# 06_-_Voltage_Sense.net
KiCad netlist of a schematic drawn in Altium Designer
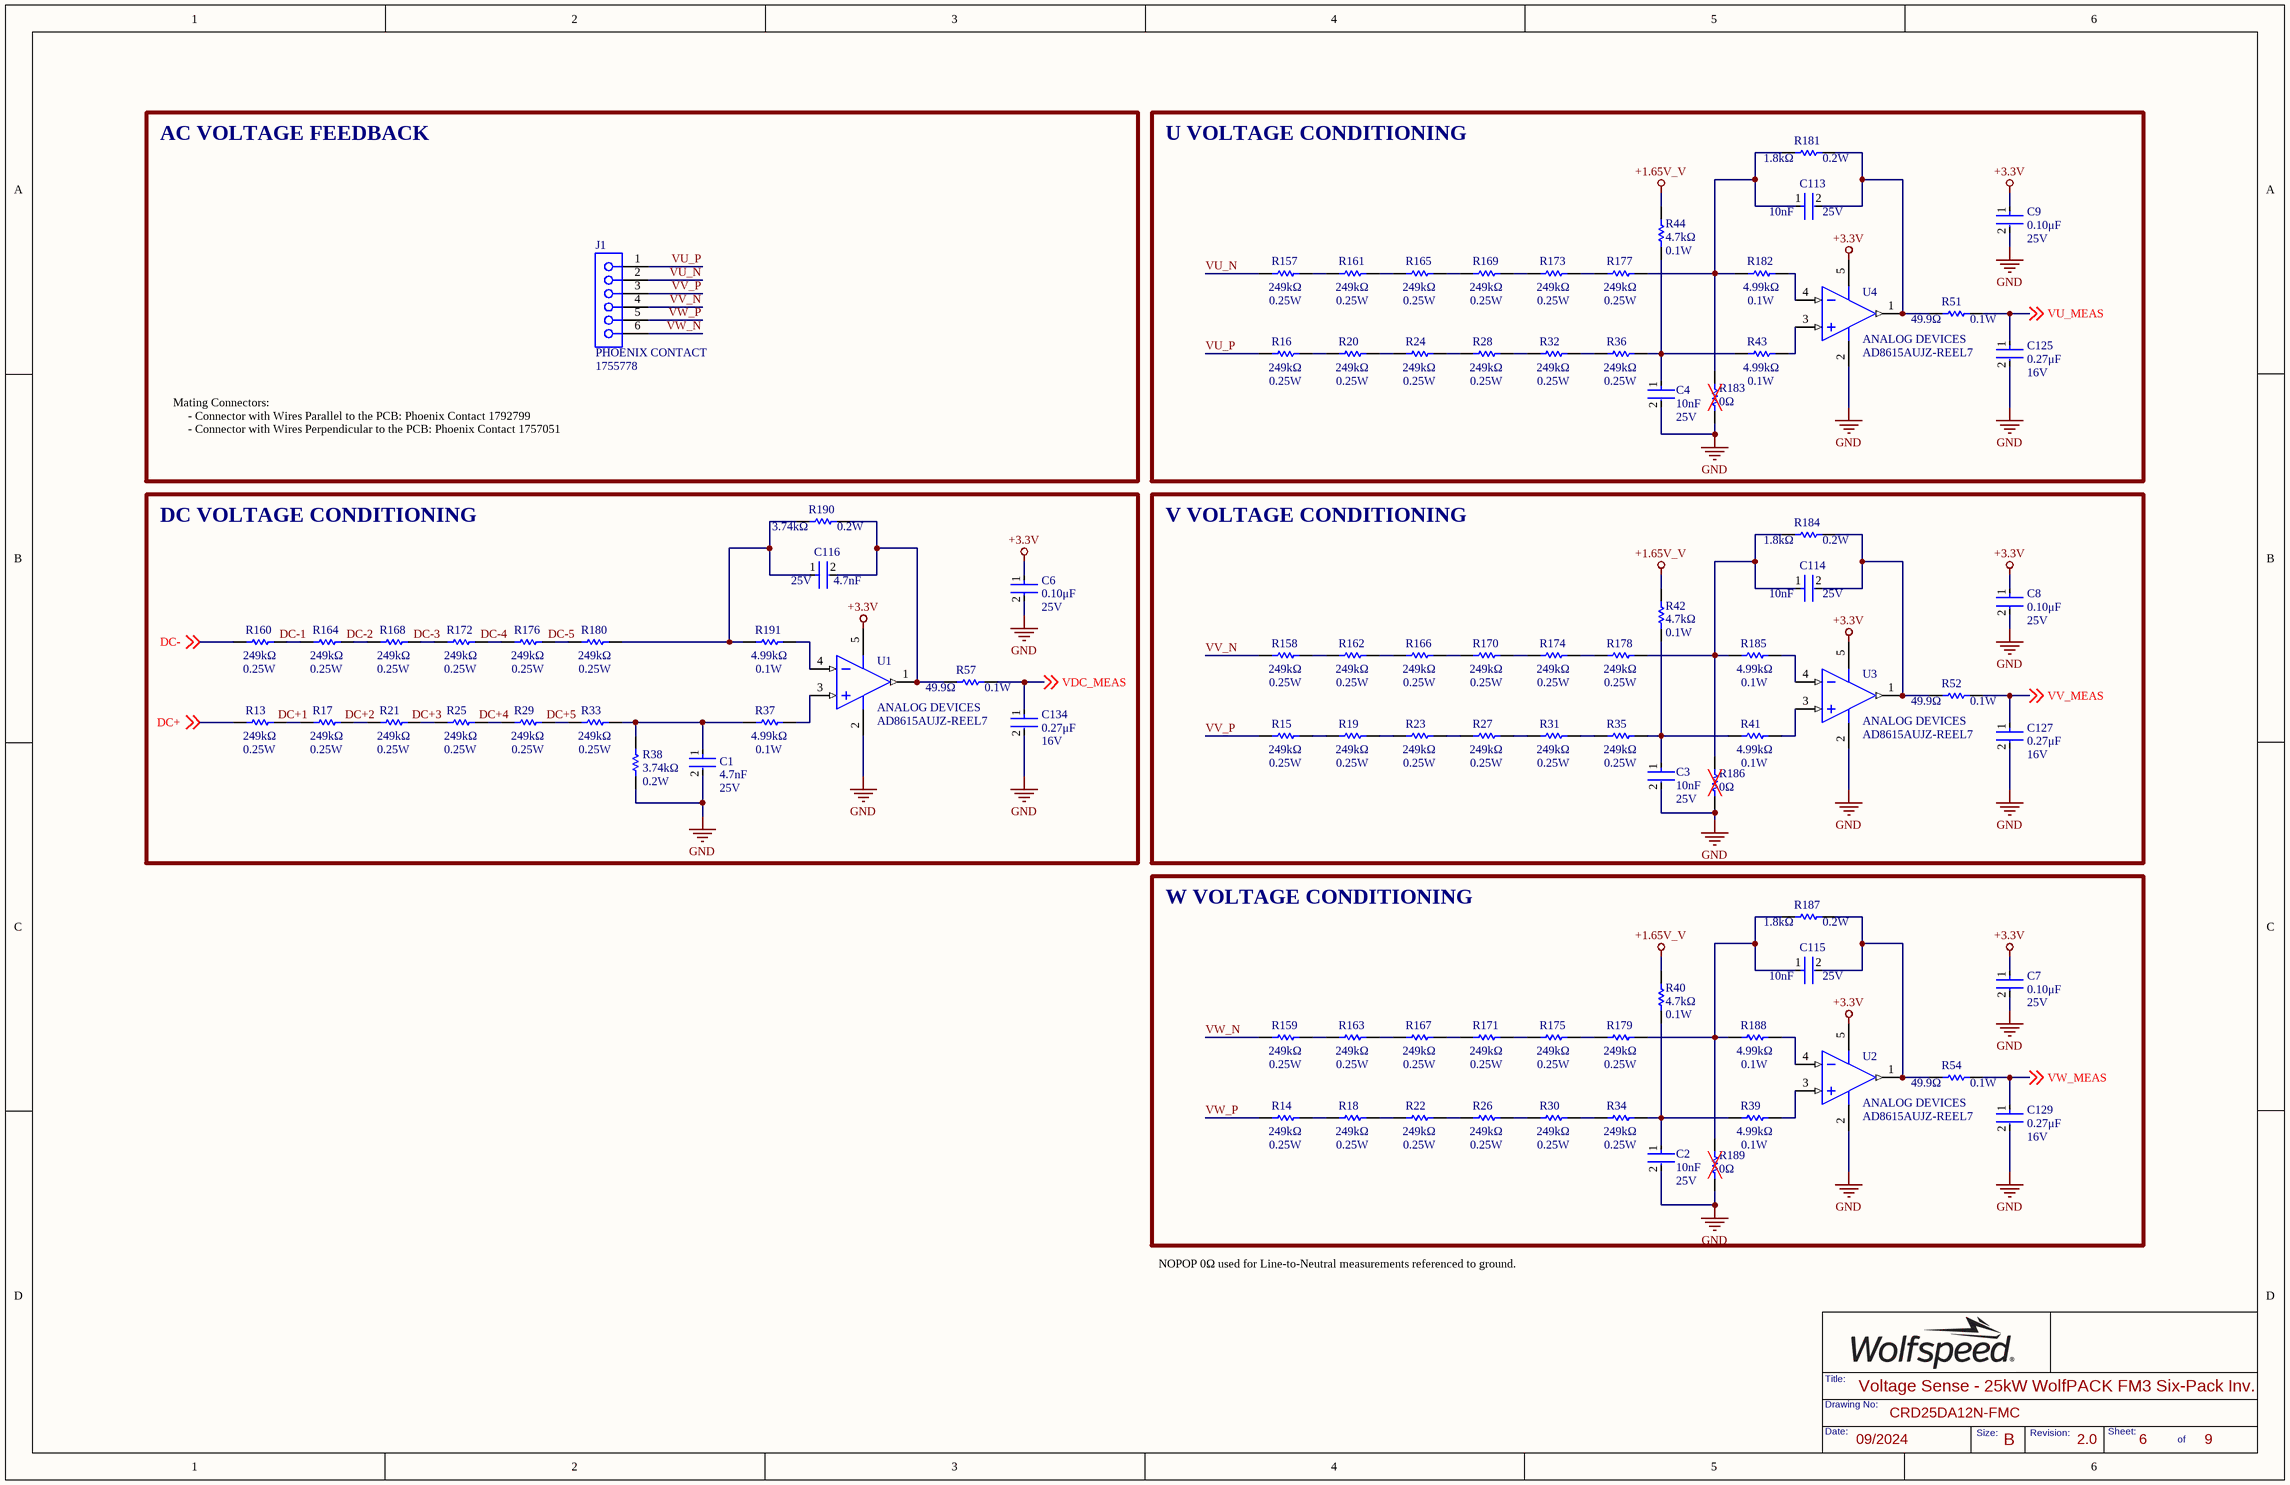
[diagram p0: 06 - Voltage Sense.SchDoc]

(export (version "E")
  (design (tool "Eeschema 10.0.6"))
  (components
    (comp (ref "C1")
      (value "C0603C472K3RAC7867")
      (footprint "FP-C0603C-CF-IPC_B")
      (description "CAP CER 4700PF 25V 10% X7R 0603")
      (fields
        (field (name "MANUFACTURER") "KEMET")
        (field (name "MANUFACTURER PART NUMBER") "C0603C472K3RACTU")
        (field (name "VOLTAGE RATING") "25V")
        (field (name "CAPACITANCE") "4.7nF")
      )
      (libsource (lib "Inverter_25kW") (part "C0603C472K3RAC7867"))
    )
    (comp (ref "C2")
      (value "10nF")
      (footprint "FP-C0603C-CF-IPC_B")
      (description "CAP CER 10000PF 25V X7R 0603")
      (fields
        (field (name "MANUFACTURER") "SAMSUNG")
        (field (name "MANUFACTURER PART NUMBER") "CL10B103KA8WPNC")
        (field (name "VOLTAGE RATING") "25V")
      )
      (libsource (lib "Inverter_25kW") (part "CL10B103KA8WPNC"))
    )
    (comp (ref "C3")
      (value "10nF")
      (footprint "FP-C0603C-CF-IPC_B")
      (description "CAP CER 10000PF 25V X7R 0603")
      (fields
        (field (name "MANUFACTURER") "SAMSUNG")
        (field (name "MANUFACTURER PART NUMBER") "CL10B103KA8WPNC")
        (field (name "VOLTAGE RATING") "25V")
      )
      (libsource (lib "Inverter_25kW") (part "CL10B103KA8WPNC"))
    )
    (comp (ref "C4")
      (value "10nF")
      (footprint "FP-C0603C-CF-IPC_B")
      (description "CAP CER 10000PF 25V X7R 0603")
      (fields
        (field (name "MANUFACTURER") "SAMSUNG")
        (field (name "MANUFACTURER PART NUMBER") "CL10B103KA8WPNC")
        (field (name "VOLTAGE RATING") "25V")
      )
      (libsource (lib "Inverter_25kW") (part "CL10B103KA8WPNC"))
    )
    (comp (ref "C6")
      (value "C0603C104K3RACTU")
      (footprint "FP-C0603C-CF-IPC_B")
      (description "CAP CER 0.1UF 25V X7R 0603")
      (fields
        (field (name "VOLTAGE RATING") "25V")
        (field (name "OCTOPART") "https://octopart.com/c0603c104k3ractu-kemet-127541")
        (field (name "MANUFACTURER") "KEMET")
        (field (name "CAPACITANCE") "0.10μF")
      )
      (libsource (lib "Altium Content Vault") (part "b4654b650e69147ec39a6b967a45e02"))
    )
    (comp (ref "C7")
      (value "C0603C104K3RACTU")
      (footprint "FP-C0603C-CF-IPC_B")
      (description "CAP CER 0.1UF 25V X7R 0603")
      (fields
        (field (name "VOLTAGE RATING") "25V")
        (field (name "OCTOPART") "https://octopart.com/c0603c104k3ractu-kemet-127541")
        (field (name "MANUFACTURER") "KEMET")
        (field (name "CAPACITANCE") "0.10μF")
      )
      (libsource (lib "Altium Content Vault") (part "b4654b650e69147ec39a6b967a45e02"))
    )
    (comp (ref "C8")
      (value "C0603C104K3RACTU")
      (footprint "FP-C0603C-CF-IPC_B")
      (description "CAP CER 0.1UF 25V X7R 0603")
      (fields
        (field (name "VOLTAGE RATING") "25V")
        (field (name "OCTOPART") "https://octopart.com/c0603c104k3ractu-kemet-127541")
        (field (name "MANUFACTURER") "KEMET")
        (field (name "CAPACITANCE") "0.10μF")
      )
      (libsource (lib "Altium Content Vault") (part "b4654b650e69147ec39a6b967a45e02"))
    )
    (comp (ref "C9")
      (value "C0603C104K3RACTU")
      (footprint "FP-C0603C-CF-IPC_B")
      (description "CAP CER 0.1UF 25V X7R 0603")
      (fields
        (field (name "VOLTAGE RATING") "25V")
        (field (name "OCTOPART") "https://octopart.com/c0603c104k3ractu-kemet-127541")
        (field (name "MANUFACTURER") "KEMET")
        (field (name "CAPACITANCE") "0.10μF")
      )
      (libsource (lib "Altium Content Vault") (part "b4654b650e69147ec39a6b967a45e02"))
    )
    (comp (ref "C113")
      (value "10nF")
      (footprint "FP-C0603C-CF-IPC_B")
      (description "CAP CER 10000PF 25V X7R 0603")
      (fields
        (field (name "MANUFACTURER") "SAMSUNG")
        (field (name "MANUFACTURER PART NUMBER") "CL10B103KA8WPNC")
        (field (name "VOLTAGE RATING") "25V")
      )
      (libsource (lib "Inverter_25kW") (part "CL10B103KA8WPNC"))
    )
    (comp (ref "C114")
      (value "10nF")
      (footprint "FP-C0603C-CF-IPC_B")
      (description "CAP CER 10000PF 25V X7R 0603")
      (fields
        (field (name "MANUFACTURER") "SAMSUNG")
        (field (name "MANUFACTURER PART NUMBER") "CL10B103KA8WPNC")
        (field (name "VOLTAGE RATING") "25V")
      )
      (libsource (lib "Inverter_25kW") (part "CL10B103KA8WPNC"))
    )
    (comp (ref "C115")
      (value "10nF")
      (footprint "FP-C0603C-CF-IPC_B")
      (description "CAP CER 10000PF 25V X7R 0603")
      (fields
        (field (name "MANUFACTURER") "SAMSUNG")
        (field (name "MANUFACTURER PART NUMBER") "CL10B103KA8WPNC")
        (field (name "VOLTAGE RATING") "25V")
      )
      (libsource (lib "Inverter_25kW") (part "CL10B103KA8WPNC"))
    )
    (comp (ref "C116")
      (value "C0603C472K3RAC7867")
      (footprint "FP-C0603C-CF-IPC_B")
      (description "CAP CER 4700PF 25V 10% X7R 0603")
      (fields
        (field (name "MANUFACTURER") "KEMET")
        (field (name "MANUFACTURER PART NUMBER") "C0603C472K3RACTU")
        (field (name "VOLTAGE RATING") "25V")
        (field (name "CAPACITANCE") "4.7nF")
      )
      (libsource (lib "Inverter_25kW") (part "C0603C472K3RAC7867"))
    )
    (comp (ref "C125")
      (value "GCM188R71C274KA37D")
      (footprint "FP-GCM188-0_1-IPC_A")
      (description "CAP CER 0.27UF 16V X7R 0603")
      (fields
        (field (name "VOLTAGE RATING (DC)") "16V")
        (field (name "CAPACITANCE") "0.27μF")
        (field (name "TOLERANCE") "10%")
        (field (name "MANUFACTURER") "MURATA")
      )
      (libsource (lib "Altium Content Vault") (part "02cd4be3c70576c341d710602a673aa"))
    )
    (comp (ref "C127")
      (value "GCM188R71C274KA37D")
      (footprint "FP-GCM188-0_1-IPC_A")
      (description "CAP CER 0.27UF 16V X7R 0603")
      (fields
        (field (name "VOLTAGE RATING (DC)") "16V")
        (field (name "CAPACITANCE") "0.27μF")
        (field (name "TOLERANCE") "10%")
        (field (name "MANUFACTURER") "MURATA")
      )
      (libsource (lib "Altium Content Vault") (part "02cd4be3c70576c341d710602a673aa"))
    )
    (comp (ref "C129")
      (value "GCM188R71C274KA37D")
      (footprint "FP-GCM188-0_1-IPC_A")
      (description "CAP CER 0.27UF 16V X7R 0603")
      (fields
        (field (name "VOLTAGE RATING (DC)") "16V")
        (field (name "CAPACITANCE") "0.27μF")
        (field (name "TOLERANCE") "10%")
        (field (name "MANUFACTURER") "MURATA")
      )
      (libsource (lib "Altium Content Vault") (part "02cd4be3c70576c341d710602a673aa"))
    )
    (comp (ref "C134")
      (value "GCM188R71C274KA37D")
      (footprint "FP-GCM188-0_1-IPC_A")
      (description "CAP CER 0.27UF 16V X7R 0603")
      (fields
        (field (name "VOLTAGE RATING (DC)") "16V")
        (field (name "CAPACITANCE") "0.27μF")
        (field (name "TOLERANCE") "10%")
        (field (name "MANUFACTURER") "MURATA")
      )
      (libsource (lib "Altium Content Vault") (part "02cd4be3c70576c341d710602a673aa"))
    )
    (comp (ref "J1")
      (value "1755778")
      (footprint "Inverter_25kW:1755778")
      (description "TERM BLOCK HDR 6POS VERT 5.08MM")
      (fields
        (field (name "MANUFACTURER") "PHOENIX CONTACT")
        (field (name "VOLTAGE") "300V")
        (field (name "MANUFACTURER PRINT") "PHOENIX CONTACT")
      )
      (libsource (lib "Inverter_25kW") (part "1755778"))
    )
    (comp (ref "R13")
      (value "TNPW1206249KBEEA")
      (footprint "RESC3216X65X50NL15T25")
      (description "RES 249K OHM 0.1% 1/4W 1206")
      (fields
        (field (name "MANUFACTURER") "VISHAY DALE")
        (field (name "RESISTANCE") "249kΩ")
        (field (name "POWER") "0.25W")
      )
      (libsource (lib "Altium Content Vault") (part "RES"))
    )
    (comp (ref "R14")
      (value "TNPW1206249KBEEA")
      (footprint "RESC3216X65X50NL15T25")
      (description "RES 249K OHM 0.1% 1/4W 1206")
      (fields
        (field (name "MANUFACTURER") "VISHAY DALE")
        (field (name "RESISTANCE") "249kΩ")
        (field (name "POWER") "0.25W")
      )
      (libsource (lib "Altium Content Vault") (part "RES"))
    )
    (comp (ref "R15")
      (value "TNPW1206249KBEEA")
      (footprint "RESC3216X65X50NL15T25")
      (description "RES 249K OHM 0.1% 1/4W 1206")
      (fields
        (field (name "MANUFACTURER") "VISHAY DALE")
        (field (name "RESISTANCE") "249kΩ")
        (field (name "POWER") "0.25W")
      )
      (libsource (lib "Altium Content Vault") (part "RES"))
    )
    (comp (ref "R16")
      (value "TNPW1206249KBEEA")
      (footprint "RESC3216X65X50NL15T25")
      (description "RES 249K OHM 0.1% 1/4W 1206")
      (fields
        (field (name "MANUFACTURER") "VISHAY DALE")
        (field (name "RESISTANCE") "249kΩ")
        (field (name "POWER") "0.25W")
      )
      (libsource (lib "Altium Content Vault") (part "RES"))
    )
    (comp (ref "R17")
      (value "TNPW1206249KBEEA")
      (footprint "RESC3216X65X50NL15T25")
      (description "RES 249K OHM 0.1% 1/4W 1206")
      (fields
        (field (name "MANUFACTURER") "VISHAY DALE")
        (field (name "RESISTANCE") "249kΩ")
        (field (name "POWER") "0.25W")
      )
      (libsource (lib "Altium Content Vault") (part "RES"))
    )
    (comp (ref "R18")
      (value "TNPW1206249KBEEA")
      (footprint "RESC3216X65X50NL15T25")
      (description "RES 249K OHM 0.1% 1/4W 1206")
      (fields
        (field (name "MANUFACTURER") "VISHAY DALE")
        (field (name "RESISTANCE") "249kΩ")
        (field (name "POWER") "0.25W")
      )
      (libsource (lib "Altium Content Vault") (part "RES"))
    )
    (comp (ref "R19")
      (value "TNPW1206249KBEEA")
      (footprint "RESC3216X65X50NL15T25")
      (description "RES 249K OHM 0.1% 1/4W 1206")
      (fields
        (field (name "MANUFACTURER") "VISHAY DALE")
        (field (name "RESISTANCE") "249kΩ")
        (field (name "POWER") "0.25W")
      )
      (libsource (lib "Altium Content Vault") (part "RES"))
    )
    (comp (ref "R20")
      (value "TNPW1206249KBEEA")
      (footprint "RESC3216X65X50NL15T25")
      (description "RES 249K OHM 0.1% 1/4W 1206")
      (fields
        (field (name "MANUFACTURER") "VISHAY DALE")
        (field (name "RESISTANCE") "249kΩ")
        (field (name "POWER") "0.25W")
      )
      (libsource (lib "Altium Content Vault") (part "RES"))
    )
    (comp (ref "R21")
      (value "TNPW1206249KBEEA")
      (footprint "RESC3216X65X50NL15T25")
      (description "RES 249K OHM 0.1% 1/4W 1206")
      (fields
        (field (name "MANUFACTURER") "VISHAY DALE")
        (field (name "RESISTANCE") "249kΩ")
        (field (name "POWER") "0.25W")
      )
      (libsource (lib "Altium Content Vault") (part "RES"))
    )
    (comp (ref "R22")
      (value "TNPW1206249KBEEA")
      (footprint "RESC3216X65X50NL15T25")
      (description "RES 249K OHM 0.1% 1/4W 1206")
      (fields
        (field (name "MANUFACTURER") "VISHAY DALE")
        (field (name "RESISTANCE") "249kΩ")
        (field (name "POWER") "0.25W")
      )
      (libsource (lib "Altium Content Vault") (part "RES"))
    )
    (comp (ref "R23")
      (value "TNPW1206249KBEEA")
      (footprint "RESC3216X65X50NL15T25")
      (description "RES 249K OHM 0.1% 1/4W 1206")
      (fields
        (field (name "MANUFACTURER") "VISHAY DALE")
        (field (name "RESISTANCE") "249kΩ")
        (field (name "POWER") "0.25W")
      )
      (libsource (lib "Altium Content Vault") (part "RES"))
    )
    (comp (ref "R24")
      (value "TNPW1206249KBEEA")
      (footprint "RESC3216X65X50NL15T25")
      (description "RES 249K OHM 0.1% 1/4W 1206")
      (fields
        (field (name "MANUFACTURER") "VISHAY DALE")
        (field (name "RESISTANCE") "249kΩ")
        (field (name "POWER") "0.25W")
      )
      (libsource (lib "Altium Content Vault") (part "RES"))
    )
    (comp (ref "R25")
      (value "TNPW1206249KBEEA")
      (footprint "RESC3216X65X50NL15T25")
      (description "RES 249K OHM 0.1% 1/4W 1206")
      (fields
        (field (name "MANUFACTURER") "VISHAY DALE")
        (field (name "RESISTANCE") "249kΩ")
        (field (name "POWER") "0.25W")
      )
      (libsource (lib "Altium Content Vault") (part "RES"))
    )
    (comp (ref "R26")
      (value "TNPW1206249KBEEA")
      (footprint "RESC3216X65X50NL15T25")
      (description "RES 249K OHM 0.1% 1/4W 1206")
      (fields
        (field (name "MANUFACTURER") "VISHAY DALE")
        (field (name "RESISTANCE") "249kΩ")
        (field (name "POWER") "0.25W")
      )
      (libsource (lib "Altium Content Vault") (part "RES"))
    )
    (comp (ref "R27")
      (value "TNPW1206249KBEEA")
      (footprint "RESC3216X65X50NL15T25")
      (description "RES 249K OHM 0.1% 1/4W 1206")
      (fields
        (field (name "MANUFACTURER") "VISHAY DALE")
        (field (name "RESISTANCE") "249kΩ")
        (field (name "POWER") "0.25W")
      )
      (libsource (lib "Altium Content Vault") (part "RES"))
    )
    (comp (ref "R28")
      (value "TNPW1206249KBEEA")
      (footprint "RESC3216X65X50NL15T25")
      (description "RES 249K OHM 0.1% 1/4W 1206")
      (fields
        (field (name "MANUFACTURER") "VISHAY DALE")
        (field (name "RESISTANCE") "249kΩ")
        (field (name "POWER") "0.25W")
      )
      (libsource (lib "Altium Content Vault") (part "RES"))
    )
    (comp (ref "R29")
      (value "TNPW1206249KBEEA")
      (footprint "RESC3216X65X50NL15T25")
      (description "RES 249K OHM 0.1% 1/4W 1206")
      (fields
        (field (name "MANUFACTURER") "VISHAY DALE")
        (field (name "RESISTANCE") "249kΩ")
        (field (name "POWER") "0.25W")
      )
      (libsource (lib "Altium Content Vault") (part "RES"))
    )
    (comp (ref "R30")
      (value "TNPW1206249KBEEA")
      (footprint "RESC3216X65X50NL15T25")
      (description "RES 249K OHM 0.1% 1/4W 1206")
      (fields
        (field (name "MANUFACTURER") "VISHAY DALE")
        (field (name "RESISTANCE") "249kΩ")
        (field (name "POWER") "0.25W")
      )
      (libsource (lib "Altium Content Vault") (part "RES"))
    )
    (comp (ref "R31")
      (value "TNPW1206249KBEEA")
      (footprint "RESC3216X65X50NL15T25")
      (description "RES 249K OHM 0.1% 1/4W 1206")
      (fields
        (field (name "MANUFACTURER") "VISHAY DALE")
        (field (name "RESISTANCE") "249kΩ")
        (field (name "POWER") "0.25W")
      )
      (libsource (lib "Altium Content Vault") (part "RES"))
    )
    (comp (ref "R32")
      (value "TNPW1206249KBEEA")
      (footprint "RESC3216X65X50NL15T25")
      (description "RES 249K OHM 0.1% 1/4W 1206")
      (fields
        (field (name "MANUFACTURER") "VISHAY DALE")
        (field (name "RESISTANCE") "249kΩ")
        (field (name "POWER") "0.25W")
      )
      (libsource (lib "Altium Content Vault") (part "RES"))
    )
    (comp (ref "R33")
      (value "TNPW1206249KBEEA")
      (footprint "RESC3216X65X50NL15T25")
      (description "RES 249K OHM 0.1% 1/4W 1206")
      (fields
        (field (name "MANUFACTURER") "VISHAY DALE")
        (field (name "RESISTANCE") "249kΩ")
        (field (name "POWER") "0.25W")
      )
      (libsource (lib "Altium Content Vault") (part "RES"))
    )
    (comp (ref "R34")
      (value "TNPW1206249KBEEA")
      (footprint "RESC3216X65X50NL15T25")
      (description "RES 249K OHM 0.1% 1/4W 1206")
      (fields
        (field (name "MANUFACTURER") "VISHAY DALE")
        (field (name "RESISTANCE") "249kΩ")
        (field (name "POWER") "0.25W")
      )
      (libsource (lib "Altium Content Vault") (part "RES"))
    )
    (comp (ref "R35")
      (value "TNPW1206249KBEEA")
      (footprint "RESC3216X65X50NL15T25")
      (description "RES 249K OHM 0.1% 1/4W 1206")
      (fields
        (field (name "MANUFACTURER") "VISHAY DALE")
        (field (name "RESISTANCE") "249kΩ")
        (field (name "POWER") "0.25W")
      )
      (libsource (lib "Altium Content Vault") (part "RES"))
    )
    (comp (ref "R36")
      (value "TNPW1206249KBEEA")
      (footprint "RESC3216X65X50NL15T25")
      (description "RES 249K OHM 0.1% 1/4W 1206")
      (fields
        (field (name "MANUFACTURER") "VISHAY DALE")
        (field (name "RESISTANCE") "249kΩ")
        (field (name "POWER") "0.25W")
      )
      (libsource (lib "Altium Content Vault") (part "RES"))
    )
    (comp (ref "R37")
      (value "RC0603FR-074K99L")
      (footprint "FP-MCR03-IPC_B")
      (description "RES 4.99K OHM 1% 1/10W 0603")
      (fields
        (field (name "MANUFACTURER") "YAGEO")
        (field (name "TOLERANCE") "1%")
        (field (name "POWER RATING") "0.1W")
        (field (name "RESISTANCE") "4.99kΩ")
      )
      (libsource (lib "Inverter_25kW") (part "RC0603FR-074K99L"))
    )
    (comp (ref "R38")
      (value "ERJ-PB3B3741V")
      (footprint "FP-MCR03-IPC_B")
      (description "RES SMD 3.74K OHM 0.1% 1/5W 0603")
      (fields
        (field (name "MANUFACTURER") "PANASONIC")
        (field (name "TOLERANCE") "0.1%")
        (field (name "MAX POWER DISSIPATION") "0.2W")
        (field (name "RESISTANCE") "3.74kΩ")
      )
      (libsource (lib "Inverter_25kW") (part "ERJ-PB3B3741V"))
    )
    (comp (ref "R39")
      (value "RC0603FR-074K99L")
      (footprint "FP-MCR03-IPC_B")
      (description "RES 4.99K OHM 1% 1/10W 0603")
      (fields
        (field (name "MANUFACTURER") "YAGEO")
        (field (name "TOLERANCE") "1%")
        (field (name "POWER RATING") "0.1W")
        (field (name "RESISTANCE") "4.99kΩ")
      )
      (libsource (lib "Inverter_25kW") (part "RC0603FR-074K99L"))
    )
    (comp (ref "R40")
      (value "CRCW06034K70FKTA")
      (footprint "FP-MCR03-IPC_B")
      (description "RES SMD 4.7K OHM 1% 1/10W 0603")
      (fields
        (field (name "MANUFACTURER") "VISHAY DALE")
        (field (name "TOLERANCE") "1%")
        (field (name "RESISTANCE") "4.7kΩ")
        (field (name "POWER RATING") "0.1W")
      )
      (libsource (lib "Inverter_25kW") (part "CRCW06034K70FKTA"))
    )
    (comp (ref "R41")
      (value "RC0603FR-074K99L")
      (footprint "FP-MCR03-IPC_B")
      (description "RES 4.99K OHM 1% 1/10W 0603")
      (fields
        (field (name "MANUFACTURER") "YAGEO")
        (field (name "TOLERANCE") "1%")
        (field (name "POWER RATING") "0.1W")
        (field (name "RESISTANCE") "4.99kΩ")
      )
      (libsource (lib "Inverter_25kW") (part "RC0603FR-074K99L"))
    )
    (comp (ref "R42")
      (value "CRCW06034K70FKTA")
      (footprint "FP-MCR03-IPC_B")
      (description "RES SMD 4.7K OHM 1% 1/10W 0603")
      (fields
        (field (name "MANUFACTURER") "VISHAY DALE")
        (field (name "TOLERANCE") "1%")
        (field (name "RESISTANCE") "4.7kΩ")
        (field (name "POWER RATING") "0.1W")
      )
      (libsource (lib "Inverter_25kW") (part "CRCW06034K70FKTA"))
    )
    (comp (ref "R43")
      (value "RC0603FR-074K99L")
      (footprint "FP-MCR03-IPC_B")
      (description "RES 4.99K OHM 1% 1/10W 0603")
      (fields
        (field (name "MANUFACTURER") "YAGEO")
        (field (name "TOLERANCE") "1%")
        (field (name "POWER RATING") "0.1W")
        (field (name "RESISTANCE") "4.99kΩ")
      )
      (libsource (lib "Inverter_25kW") (part "RC0603FR-074K99L"))
    )
    (comp (ref "R44")
      (value "CRCW06034K70FKTA")
      (footprint "FP-MCR03-IPC_B")
      (description "RES SMD 4.7K OHM 1% 1/10W 0603")
      (fields
        (field (name "MANUFACTURER") "VISHAY DALE")
        (field (name "TOLERANCE") "1%")
        (field (name "RESISTANCE") "4.7kΩ")
        (field (name "POWER RATING") "0.1W")
      )
      (libsource (lib "Inverter_25kW") (part "CRCW06034K70FKTA"))
    )
    (comp (ref "R51")
      (value "ERJ-3EKF49R9V")
      (footprint "FP-MCR03-IPC_B")
      (description "RES SMD 49.9 OHM 1% 1/10W 0603")
      (fields
        (field (name "MANUFACTURER") "PANASONIC")
        (field (name "TOLERANCE") "1%")
        (field (name "RESISTANCE") "49.9Ω")
        (field (name "POWER RATING") "0.1W")
      )
      (libsource (lib "Inverter_25kW") (part "ERJ-3EKF49R9V"))
    )
    (comp (ref "R52")
      (value "ERJ-3EKF49R9V")
      (footprint "FP-MCR03-IPC_B")
      (description "RES SMD 49.9 OHM 1% 1/10W 0603")
      (fields
        (field (name "MANUFACTURER") "PANASONIC")
        (field (name "TOLERANCE") "1%")
        (field (name "RESISTANCE") "49.9Ω")
        (field (name "POWER RATING") "0.1W")
      )
      (libsource (lib "Inverter_25kW") (part "ERJ-3EKF49R9V"))
    )
    (comp (ref "R54")
      (value "ERJ-3EKF49R9V")
      (footprint "FP-MCR03-IPC_B")
      (description "RES SMD 49.9 OHM 1% 1/10W 0603")
      (fields
        (field (name "MANUFACTURER") "PANASONIC")
        (field (name "TOLERANCE") "1%")
        (field (name "RESISTANCE") "49.9Ω")
        (field (name "POWER RATING") "0.1W")
      )
      (libsource (lib "Inverter_25kW") (part "ERJ-3EKF49R9V"))
    )
    (comp (ref "R57")
      (value "ERJ-3EKF49R9V")
      (footprint "FP-MCR03-IPC_B")
      (description "RES SMD 49.9 OHM 1% 1/10W 0603")
      (fields
        (field (name "MANUFACTURER") "PANASONIC")
        (field (name "TOLERANCE") "1%")
        (field (name "RESISTANCE") "49.9Ω")
        (field (name "POWER RATING") "0.1W")
      )
      (libsource (lib "Inverter_25kW") (part "ERJ-3EKF49R9V"))
    )
    (comp (ref "R157")
      (value "TNPW1206249KBEEA")
      (footprint "RESC3216X65X50NL15T25")
      (description "RES 249K OHM 0.1% 1/4W 1206")
      (fields
        (field (name "MANUFACTURER") "VISHAY DALE")
        (field (name "RESISTANCE") "249kΩ")
        (field (name "POWER") "0.25W")
      )
      (libsource (lib "Altium Content Vault") (part "RES"))
    )
    (comp (ref "R158")
      (value "TNPW1206249KBEEA")
      (footprint "RESC3216X65X50NL15T25")
      (description "RES 249K OHM 0.1% 1/4W 1206")
      (fields
        (field (name "MANUFACTURER") "VISHAY DALE")
        (field (name "RESISTANCE") "249kΩ")
        (field (name "POWER") "0.25W")
      )
      (libsource (lib "Altium Content Vault") (part "RES"))
    )
    (comp (ref "R159")
      (value "TNPW1206249KBEEA")
      (footprint "RESC3216X65X50NL15T25")
      (description "RES 249K OHM 0.1% 1/4W 1206")
      (fields
        (field (name "MANUFACTURER") "VISHAY DALE")
        (field (name "RESISTANCE") "249kΩ")
        (field (name "POWER") "0.25W")
      )
      (libsource (lib "Altium Content Vault") (part "RES"))
    )
    (comp (ref "R160")
      (value "TNPW1206249KBEEA")
      (footprint "RESC3216X65X50NL15T25")
      (description "RES 249K OHM 0.1% 1/4W 1206")
      (fields
        (field (name "MANUFACTURER") "VISHAY DALE")
        (field (name "RESISTANCE") "249kΩ")
        (field (name "POWER") "0.25W")
      )
      (libsource (lib "Altium Content Vault") (part "RES"))
    )
    (comp (ref "R161")
      (value "TNPW1206249KBEEA")
      (footprint "RESC3216X65X50NL15T25")
      (description "RES 249K OHM 0.1% 1/4W 1206")
      (fields
        (field (name "MANUFACTURER") "VISHAY DALE")
        (field (name "RESISTANCE") "249kΩ")
        (field (name "POWER") "0.25W")
      )
      (libsource (lib "Altium Content Vault") (part "RES"))
    )
    (comp (ref "R162")
      (value "TNPW1206249KBEEA")
      (footprint "RESC3216X65X50NL15T25")
      (description "RES 249K OHM 0.1% 1/4W 1206")
      (fields
        (field (name "MANUFACTURER") "VISHAY DALE")
        (field (name "RESISTANCE") "249kΩ")
        (field (name "POWER") "0.25W")
      )
      (libsource (lib "Altium Content Vault") (part "RES"))
    )
    (comp (ref "R163")
      (value "TNPW1206249KBEEA")
      (footprint "RESC3216X65X50NL15T25")
      (description "RES 249K OHM 0.1% 1/4W 1206")
      (fields
        (field (name "MANUFACTURER") "VISHAY DALE")
        (field (name "RESISTANCE") "249kΩ")
        (field (name "POWER") "0.25W")
      )
      (libsource (lib "Altium Content Vault") (part "RES"))
    )
    (comp (ref "R164")
      (value "TNPW1206249KBEEA")
      (footprint "RESC3216X65X50NL15T25")
      (description "RES 249K OHM 0.1% 1/4W 1206")
      (fields
        (field (name "MANUFACTURER") "VISHAY DALE")
        (field (name "RESISTANCE") "249kΩ")
        (field (name "POWER") "0.25W")
      )
      (libsource (lib "Altium Content Vault") (part "RES"))
    )
    (comp (ref "R165")
      (value "TNPW1206249KBEEA")
      (footprint "RESC3216X65X50NL15T25")
      (description "RES 249K OHM 0.1% 1/4W 1206")
      (fields
        (field (name "MANUFACTURER") "VISHAY DALE")
        (field (name "RESISTANCE") "249kΩ")
        (field (name "POWER") "0.25W")
      )
      (libsource (lib "Altium Content Vault") (part "RES"))
    )
    (comp (ref "R166")
      (value "TNPW1206249KBEEA")
      (footprint "RESC3216X65X50NL15T25")
      (description "RES 249K OHM 0.1% 1/4W 1206")
      (fields
        (field (name "MANUFACTURER") "VISHAY DALE")
        (field (name "RESISTANCE") "249kΩ")
        (field (name "POWER") "0.25W")
      )
      (libsource (lib "Altium Content Vault") (part "RES"))
    )
    (comp (ref "R167")
      (value "TNPW1206249KBEEA")
      (footprint "RESC3216X65X50NL15T25")
      (description "RES 249K OHM 0.1% 1/4W 1206")
      (fields
        (field (name "MANUFACTURER") "VISHAY DALE")
        (field (name "RESISTANCE") "249kΩ")
        (field (name "POWER") "0.25W")
      )
      (libsource (lib "Altium Content Vault") (part "RES"))
    )
    (comp (ref "R168")
      (value "TNPW1206249KBEEA")
      (footprint "RESC3216X65X50NL15T25")
      (description "RES 249K OHM 0.1% 1/4W 1206")
      (fields
        (field (name "MANUFACTURER") "VISHAY DALE")
        (field (name "RESISTANCE") "249kΩ")
        (field (name "POWER") "0.25W")
      )
      (libsource (lib "Altium Content Vault") (part "RES"))
    )
    (comp (ref "R169")
      (value "TNPW1206249KBEEA")
      (footprint "RESC3216X65X50NL15T25")
      (description "RES 249K OHM 0.1% 1/4W 1206")
      (fields
        (field (name "MANUFACTURER") "VISHAY DALE")
        (field (name "RESISTANCE") "249kΩ")
        (field (name "POWER") "0.25W")
      )
      (libsource (lib "Altium Content Vault") (part "RES"))
    )
    (comp (ref "R170")
      (value "TNPW1206249KBEEA")
      (footprint "RESC3216X65X50NL15T25")
      (description "RES 249K OHM 0.1% 1/4W 1206")
      (fields
        (field (name "MANUFACTURER") "VISHAY DALE")
        (field (name "RESISTANCE") "249kΩ")
        (field (name "POWER") "0.25W")
      )
      (libsource (lib "Altium Content Vault") (part "RES"))
    )
    (comp (ref "R171")
      (value "TNPW1206249KBEEA")
      (footprint "RESC3216X65X50NL15T25")
      (description "RES 249K OHM 0.1% 1/4W 1206")
      (fields
        (field (name "MANUFACTURER") "VISHAY DALE")
        (field (name "RESISTANCE") "249kΩ")
        (field (name "POWER") "0.25W")
      )
      (libsource (lib "Altium Content Vault") (part "RES"))
    )
    (comp (ref "R172")
      (value "TNPW1206249KBEEA")
      (footprint "RESC3216X65X50NL15T25")
      (description "RES 249K OHM 0.1% 1/4W 1206")
      (fields
        (field (name "MANUFACTURER") "VISHAY DALE")
        (field (name "RESISTANCE") "249kΩ")
        (field (name "POWER") "0.25W")
      )
      (libsource (lib "Altium Content Vault") (part "RES"))
    )
    (comp (ref "R173")
      (value "TNPW1206249KBEEA")
      (footprint "RESC3216X65X50NL15T25")
      (description "RES 249K OHM 0.1% 1/4W 1206")
      (fields
        (field (name "MANUFACTURER") "VISHAY DALE")
        (field (name "RESISTANCE") "249kΩ")
        (field (name "POWER") "0.25W")
      )
      (libsource (lib "Altium Content Vault") (part "RES"))
    )
    (comp (ref "R174")
      (value "TNPW1206249KBEEA")
      (footprint "RESC3216X65X50NL15T25")
      (description "RES 249K OHM 0.1% 1/4W 1206")
      (fields
        (field (name "MANUFACTURER") "VISHAY DALE")
        (field (name "RESISTANCE") "249kΩ")
        (field (name "POWER") "0.25W")
      )
      (libsource (lib "Altium Content Vault") (part "RES"))
    )
    (comp (ref "R175")
      (value "TNPW1206249KBEEA")
      (footprint "RESC3216X65X50NL15T25")
      (description "RES 249K OHM 0.1% 1/4W 1206")
      (fields
        (field (name "MANUFACTURER") "VISHAY DALE")
        (field (name "RESISTANCE") "249kΩ")
        (field (name "POWER") "0.25W")
      )
      (libsource (lib "Altium Content Vault") (part "RES"))
    )
    (comp (ref "R176")
      (value "TNPW1206249KBEEA")
      (footprint "RESC3216X65X50NL15T25")
      (description "RES 249K OHM 0.1% 1/4W 1206")
      (fields
        (field (name "MANUFACTURER") "VISHAY DALE")
        (field (name "RESISTANCE") "249kΩ")
        (field (name "POWER") "0.25W")
      )
      (libsource (lib "Altium Content Vault") (part "RES"))
    )
    (comp (ref "R177")
      (value "TNPW1206249KBEEA")
      (footprint "RESC3216X65X50NL15T25")
      (description "RES 249K OHM 0.1% 1/4W 1206")
      (fields
        (field (name "MANUFACTURER") "VISHAY DALE")
        (field (name "RESISTANCE") "249kΩ")
        (field (name "POWER") "0.25W")
      )
      (libsource (lib "Altium Content Vault") (part "RES"))
    )
    (comp (ref "R178")
      (value "TNPW1206249KBEEA")
      (footprint "RESC3216X65X50NL15T25")
      (description "RES 249K OHM 0.1% 1/4W 1206")
      (fields
        (field (name "MANUFACTURER") "VISHAY DALE")
        (field (name "RESISTANCE") "249kΩ")
        (field (name "POWER") "0.25W")
      )
      (libsource (lib "Altium Content Vault") (part "RES"))
    )
    (comp (ref "R179")
      (value "TNPW1206249KBEEA")
      (footprint "RESC3216X65X50NL15T25")
      (description "RES 249K OHM 0.1% 1/4W 1206")
      (fields
        (field (name "MANUFACTURER") "VISHAY DALE")
        (field (name "RESISTANCE") "249kΩ")
        (field (name "POWER") "0.25W")
      )
      (libsource (lib "Altium Content Vault") (part "RES"))
    )
    (comp (ref "R180")
      (value "TNPW1206249KBEEA")
      (footprint "RESC3216X65X50NL15T25")
      (description "RES 249K OHM 0.1% 1/4W 1206")
      (fields
        (field (name "MANUFACTURER") "VISHAY DALE")
        (field (name "RESISTANCE") "249kΩ")
        (field (name "POWER") "0.25W")
      )
      (libsource (lib "Altium Content Vault") (part "RES"))
    )
    (comp (ref "R181")
      (value "ERJ-PB3B1801V")
      (footprint "FP-MCR03-IPC_B")
      (description "RES SMD 1.8K OHM 0.1% 1/5W 0603")
      (fields
        (field (name "MANUFACTURER") "PANASONIC")
        (field (name "TOLERANCE") "0.1%")
        (field (name "RESISTANCE") "1.8kΩ")
        (field (name "MAX POWER DISSIPATION") "0.2W")
      )
      (libsource (lib "Inverter_25kW") (part "ERJ-PB3B1801V"))
    )
    (comp (ref "R182")
      (value "RC0603FR-074K99L")
      (footprint "FP-MCR03-IPC_B")
      (description "RES 4.99K OHM 1% 1/10W 0603")
      (fields
        (field (name "MANUFACTURER") "YAGEO")
        (field (name "TOLERANCE") "1%")
        (field (name "POWER RATING") "0.1W")
        (field (name "RESISTANCE") "4.99kΩ")
      )
      (libsource (lib "Inverter_25kW") (part "RC0603FR-074K99L"))
    )
    (comp (ref "R183")
      (value "CRCW06030000Z0EB")
      (footprint "FP-MCR03-IPC_B")
      (description "RES SMD 0 OHM JUMPER 1/10W 0603")
      (fields
        (field (name "MANUFACTURER") "VISHAY DALE")
        (field (name "MANUFACTURER PART NUMBER") "CRCW06030000Z0EBC")
        (field (name "RESISTANCE") "0Ω")
      )
      (libsource (lib "Inverter_25kW") (part "CRCW06030000Z0EB"))
    )
    (comp (ref "R184")
      (value "ERJ-PB3B1801V")
      (footprint "FP-MCR03-IPC_B")
      (description "RES SMD 1.8K OHM 0.1% 1/5W 0603")
      (fields
        (field (name "MANUFACTURER") "PANASONIC")
        (field (name "TOLERANCE") "0.1%")
        (field (name "RESISTANCE") "1.8kΩ")
        (field (name "MAX POWER DISSIPATION") "0.2W")
      )
      (libsource (lib "Inverter_25kW") (part "ERJ-PB3B1801V"))
    )
    (comp (ref "R185")
      (value "RC0603FR-074K99L")
      (footprint "FP-MCR03-IPC_B")
      (description "RES 4.99K OHM 1% 1/10W 0603")
      (fields
        (field (name "MANUFACTURER") "YAGEO")
        (field (name "TOLERANCE") "1%")
        (field (name "POWER RATING") "0.1W")
        (field (name "RESISTANCE") "4.99kΩ")
      )
      (libsource (lib "Inverter_25kW") (part "RC0603FR-074K99L"))
    )
    (comp (ref "R186")
      (value "CRCW06030000Z0EB")
      (footprint "FP-MCR03-IPC_B")
      (description "RES SMD 0 OHM JUMPER 1/10W 0603")
      (fields
        (field (name "MANUFACTURER") "VISHAY DALE")
        (field (name "MANUFACTURER PART NUMBER") "CRCW06030000Z0EBC")
        (field (name "RESISTANCE") "0Ω")
      )
      (libsource (lib "Inverter_25kW") (part "CRCW06030000Z0EB"))
    )
    (comp (ref "R187")
      (value "ERJ-PB3B1801V")
      (footprint "FP-MCR03-IPC_B")
      (description "RES SMD 1.8K OHM 0.1% 1/5W 0603")
      (fields
        (field (name "MANUFACTURER") "PANASONIC")
        (field (name "TOLERANCE") "0.1%")
        (field (name "RESISTANCE") "1.8kΩ")
        (field (name "MAX POWER DISSIPATION") "0.2W")
      )
      (libsource (lib "Inverter_25kW") (part "ERJ-PB3B1801V"))
    )
    (comp (ref "R188")
      (value "RC0603FR-074K99L")
      (footprint "FP-MCR03-IPC_B")
      (description "RES 4.99K OHM 1% 1/10W 0603")
      (fields
        (field (name "MANUFACTURER") "YAGEO")
        (field (name "TOLERANCE") "1%")
        (field (name "POWER RATING") "0.1W")
        (field (name "RESISTANCE") "4.99kΩ")
      )
      (libsource (lib "Inverter_25kW") (part "RC0603FR-074K99L"))
    )
    (comp (ref "R189")
      (value "CRCW06030000Z0EB")
      (footprint "FP-MCR03-IPC_B")
      (description "RES SMD 0 OHM JUMPER 1/10W 0603")
      (fields
        (field (name "MANUFACTURER") "VISHAY DALE")
        (field (name "MANUFACTURER PART NUMBER") "CRCW06030000Z0EBC")
        (field (name "RESISTANCE") "0Ω")
      )
      (libsource (lib "Inverter_25kW") (part "CRCW06030000Z0EB"))
    )
    (comp (ref "R190")
      (value "ERJ-PB3B3741V")
      (footprint "FP-MCR03-IPC_B")
      (description "RES SMD 3.74K OHM 0.1% 1/5W 0603")
      (fields
        (field (name "MANUFACTURER") "PANASONIC")
        (field (name "TOLERANCE") "0.1%")
        (field (name "MAX POWER DISSIPATION") "0.2W")
        (field (name "RESISTANCE") "3.74kΩ")
      )
      (libsource (lib "Inverter_25kW") (part "ERJ-PB3B3741V"))
    )
    (comp (ref "R191")
      (value "RC0603FR-074K99L")
      (footprint "FP-MCR03-IPC_B")
      (description "RES 4.99K OHM 1% 1/10W 0603")
      (fields
        (field (name "MANUFACTURER") "YAGEO")
        (field (name "TOLERANCE") "1%")
        (field (name "POWER RATING") "0.1W")
        (field (name "RESISTANCE") "4.99kΩ")
      )
      (libsource (lib "Inverter_25kW") (part "RC0603FR-074K99L"))
    )
    (comp (ref "U1")
      (value "AD8615AUJZ-REEL7")
      (footprint "ADI-UJ-5_M")
      (description "IC OPAMP GP 1 CIRCUIT TSOT23-5")
      (fields
        (field (name "MANUFACTURER") "ANALOG DEVICES")
        (field (name "GENERIC PART NUMBER") "AD8615")
        (field (name "MANUFACTURER PART NUMBER") "AD8615AUJZ-REEL7")
      )
      (libsource (lib "Altium Content Vault") (part "ADI-ADxxxx-X-5"))
    )
    (comp (ref "U2")
      (value "AD8615AUJZ-REEL7")
      (footprint "ADI-UJ-5_M")
      (description "IC OPAMP GP 1 CIRCUIT TSOT23-5")
      (fields
        (field (name "MANUFACTURER") "ANALOG DEVICES")
        (field (name "GENERIC PART NUMBER") "AD8615")
        (field (name "MANUFACTURER PART NUMBER") "AD8615AUJZ-REEL7")
      )
      (libsource (lib "Altium Content Vault") (part "ADI-ADxxxx-X-5"))
    )
    (comp (ref "U3")
      (value "AD8615AUJZ-REEL7")
      (footprint "ADI-UJ-5_M")
      (description "IC OPAMP GP 1 CIRCUIT TSOT23-5")
      (fields
        (field (name "MANUFACTURER") "ANALOG DEVICES")
        (field (name "GENERIC PART NUMBER") "AD8615")
        (field (name "MANUFACTURER PART NUMBER") "AD8615AUJZ-REEL7")
      )
      (libsource (lib "Altium Content Vault") (part "ADI-ADxxxx-X-5"))
    )
    (comp (ref "U4")
      (value "AD8615AUJZ-REEL7")
      (footprint "ADI-UJ-5_M")
      (description "IC OPAMP GP 1 CIRCUIT TSOT23-5")
      (fields
        (field (name "MANUFACTURER") "ANALOG DEVICES")
        (field (name "GENERIC PART NUMBER") "AD8615")
        (field (name "MANUFACTURER PART NUMBER") "AD8615AUJZ-REEL7")
      )
      (libsource (lib "Altium Content Vault") (part "ADI-ADxxxx-X-5"))
    )
  )
  (nets
    (net (code "1") (name "+1.65V_V") (class "Default")
      (node (ref "R40") (pin "2") (pinfunction "2_2") (pintype "passive"))
      (node (ref "R42") (pin "2") (pinfunction "2_2") (pintype "passive"))
      (node (ref "R44") (pin "2") (pinfunction "2_2") (pintype "passive"))
    )
    (net (code "2") (name "+3.3V") (class "Default")
      (node (ref "C6") (pin "1") (pinfunction "1_1") (pintype "passive"))
      (node (ref "C7") (pin "1") (pinfunction "1_1") (pintype "passive"))
      (node (ref "C8") (pin "1") (pinfunction "1_1") (pintype "passive"))
      (node (ref "C9") (pin "1") (pinfunction "1_1") (pintype "passive"))
      (node (ref "U1") (pin "5") (pinfunction "+V_5") (pintype "power_in"))
      (node (ref "U2") (pin "5") (pinfunction "+V_5") (pintype "power_in"))
      (node (ref "U3") (pin "5") (pinfunction "+V_5") (pintype "power_in"))
      (node (ref "U4") (pin "5") (pinfunction "+V_5") (pintype "power_in"))
    )
    (net (code "3") (name "/DC+1") (class "Default")
      (node (ref "R13") (pin "2") (pinfunction "2_2") (pintype "passive"))
      (node (ref "R17") (pin "1") (pinfunction "1_1") (pintype "passive"))
    )
    (net (code "4") (name "/DC+2") (class "Default")
      (node (ref "R17") (pin "2") (pinfunction "2_2") (pintype "passive"))
      (node (ref "R21") (pin "1") (pinfunction "1_1") (pintype "passive"))
    )
    (net (code "5") (name "/DC+3") (class "Default")
      (node (ref "R21") (pin "2") (pinfunction "2_2") (pintype "passive"))
      (node (ref "R25") (pin "1") (pinfunction "1_1") (pintype "passive"))
    )
    (net (code "6") (name "/DC+4") (class "Default")
      (node (ref "R25") (pin "2") (pinfunction "2_2") (pintype "passive"))
      (node (ref "R29") (pin "1") (pinfunction "1_1") (pintype "passive"))
    )
    (net (code "7") (name "/DC+5") (class "Default")
      (node (ref "R29") (pin "2") (pinfunction "2_2") (pintype "passive"))
      (node (ref "R33") (pin "1") (pinfunction "1_1") (pintype "passive"))
    )
    (net (code "8") (name "/DC-1") (class "Default")
      (node (ref "R160") (pin "2") (pinfunction "2_2") (pintype "passive"))
      (node (ref "R164") (pin "1") (pinfunction "1_1") (pintype "passive"))
    )
    (net (code "9") (name "/DC-2") (class "Default")
      (node (ref "R164") (pin "2") (pinfunction "2_2") (pintype "passive"))
      (node (ref "R168") (pin "1") (pinfunction "1_1") (pintype "passive"))
    )
    (net (code "10") (name "/DC-3") (class "Default")
      (node (ref "R168") (pin "2") (pinfunction "2_2") (pintype "passive"))
      (node (ref "R172") (pin "1") (pinfunction "1_1") (pintype "passive"))
    )
    (net (code "11") (name "/DC-4") (class "Default")
      (node (ref "R172") (pin "2") (pinfunction "2_2") (pintype "passive"))
      (node (ref "R176") (pin "1") (pinfunction "1_1") (pintype "passive"))
    )
    (net (code "12") (name "/DC-5") (class "Default")
      (node (ref "R176") (pin "2") (pinfunction "2_2") (pintype "passive"))
      (node (ref "R180") (pin "1") (pinfunction "1_1") (pintype "passive"))
    )
    (net (code "13") (name "/VU_N") (class "Default")
      (node (ref "J1") (pin "2") (pinfunction "2_2") (pintype "passive"))
      (node (ref "R157") (pin "1") (pinfunction "1_1") (pintype "passive"))
    )
    (net (code "14") (name "/VU_P") (class "Default")
      (node (ref "J1") (pin "1") (pinfunction "1_1") (pintype "passive"))
      (node (ref "R16") (pin "1") (pinfunction "1_1") (pintype "passive"))
    )
    (net (code "15") (name "/VV_N") (class "Default")
      (node (ref "J1") (pin "4") (pinfunction "4_4") (pintype "passive"))
      (node (ref "R158") (pin "1") (pinfunction "1_1") (pintype "passive"))
    )
    (net (code "16") (name "/VV_P") (class "Default")
      (node (ref "J1") (pin "3") (pinfunction "3_3") (pintype "passive"))
      (node (ref "R15") (pin "1") (pinfunction "1_1") (pintype "passive"))
    )
    (net (code "17") (name "/VW_N") (class "Default")
      (node (ref "J1") (pin "6") (pinfunction "6_6") (pintype "passive"))
      (node (ref "R159") (pin "1") (pinfunction "1_1") (pintype "passive"))
    )
    (net (code "18") (name "/VW_P") (class "Default")
      (node (ref "J1") (pin "5") (pinfunction "5_5") (pintype "passive"))
      (node (ref "R14") (pin "1") (pinfunction "1_1") (pintype "passive"))
    )
    (net (code "19") (name "DC+") (class "Default")
      (node (ref "R13") (pin "1") (pinfunction "1_1") (pintype "passive"))
    )
    (net (code "20") (name "DC-") (class "Default")
      (node (ref "R160") (pin "1") (pinfunction "1_1") (pintype "passive"))
    )
    (net (code "21") (name "GND") (class "Default")
      (node (ref "C1") (pin "2") (pinfunction "2_2") (pintype "passive"))
      (node (ref "C125") (pin "2") (pinfunction "2_2") (pintype "passive"))
      (node (ref "C127") (pin "2") (pinfunction "2_2") (pintype "passive"))
      (node (ref "C129") (pin "2") (pinfunction "2_2") (pintype "passive"))
      (node (ref "C134") (pin "2") (pinfunction "2_2") (pintype "passive"))
      (node (ref "C2") (pin "2") (pinfunction "2_2") (pintype "passive"))
      (node (ref "C3") (pin "2") (pinfunction "2_2") (pintype "passive"))
      (node (ref "C4") (pin "2") (pinfunction "2_2") (pintype "passive"))
      (node (ref "C6") (pin "2") (pinfunction "2_2") (pintype "passive"))
      (node (ref "C7") (pin "2") (pinfunction "2_2") (pintype "passive"))
      (node (ref "C8") (pin "2") (pinfunction "2_2") (pintype "passive"))
      (node (ref "C9") (pin "2") (pinfunction "2_2") (pintype "passive"))
      (node (ref "R183") (pin "1") (pinfunction "1_1") (pintype "passive"))
      (node (ref "R186") (pin "1") (pinfunction "1_1") (pintype "passive"))
      (node (ref "R189") (pin "1") (pinfunction "1_1") (pintype "passive"))
      (node (ref "R38") (pin "1") (pinfunction "1_1") (pintype "passive"))
      (node (ref "U1") (pin "2") (pinfunction "-V_2") (pintype "power_in"))
      (node (ref "U2") (pin "2") (pinfunction "-V_2") (pintype "power_in"))
      (node (ref "U3") (pin "2") (pinfunction "-V_2") (pintype "power_in"))
      (node (ref "U4") (pin "2") (pinfunction "-V_2") (pintype "power_in"))
    )
    (net (code "22") (name "Net-(C1-Pad1)") (class "Default")
      (node (ref "C1") (pin "1") (pinfunction "1_1") (pintype "passive"))
      (node (ref "R33") (pin "2") (pinfunction "2_2") (pintype "passive"))
      (node (ref "R37") (pin "1") (pinfunction "1_1") (pintype "passive"))
      (node (ref "R38") (pin "2") (pinfunction "2_2") (pintype "passive"))
    )
    (net (code "23") (name "Net-(C2-Pad1)") (class "Default")
      (node (ref "C2") (pin "1") (pinfunction "1_1") (pintype "passive"))
      (node (ref "R34") (pin "2") (pinfunction "2_2") (pintype "passive"))
      (node (ref "R39") (pin "1") (pinfunction "1_1") (pintype "passive"))
      (node (ref "R40") (pin "1") (pinfunction "1_1") (pintype "passive"))
    )
    (net (code "24") (name "Net-(C3-Pad1)") (class "Default")
      (node (ref "C3") (pin "1") (pinfunction "1_1") (pintype "passive"))
      (node (ref "R35") (pin "2") (pinfunction "2_2") (pintype "passive"))
      (node (ref "R41") (pin "1") (pinfunction "1_1") (pintype "passive"))
      (node (ref "R42") (pin "1") (pinfunction "1_1") (pintype "passive"))
    )
    (net (code "25") (name "Net-(C4-Pad1)") (class "Default")
      (node (ref "C4") (pin "1") (pinfunction "1_1") (pintype "passive"))
      (node (ref "R36") (pin "2") (pinfunction "2_2") (pintype "passive"))
      (node (ref "R43") (pin "1") (pinfunction "1_1") (pintype "passive"))
      (node (ref "R44") (pin "1") (pinfunction "1_1") (pintype "passive"))
    )
    (net (code "26") (name "Net-(C113-Pad1)") (class "Default")
      (node (ref "C113") (pin "1") (pinfunction "1_1") (pintype "passive"))
      (node (ref "R177") (pin "2") (pinfunction "2_2") (pintype "passive"))
      (node (ref "R181") (pin "2") (pinfunction "2_2") (pintype "passive"))
      (node (ref "R182") (pin "1") (pinfunction "1_1") (pintype "passive"))
      (node (ref "R183") (pin "2") (pinfunction "2_2") (pintype "passive"))
    )
    (net (code "27") (name "Net-(C114-Pad1)") (class "Default")
      (node (ref "C114") (pin "1") (pinfunction "1_1") (pintype "passive"))
      (node (ref "R178") (pin "2") (pinfunction "2_2") (pintype "passive"))
      (node (ref "R184") (pin "2") (pinfunction "2_2") (pintype "passive"))
      (node (ref "R185") (pin "1") (pinfunction "1_1") (pintype "passive"))
      (node (ref "R186") (pin "2") (pinfunction "2_2") (pintype "passive"))
    )
    (net (code "28") (name "Net-(C115-Pad1)") (class "Default")
      (node (ref "C115") (pin "1") (pinfunction "1_1") (pintype "passive"))
      (node (ref "R179") (pin "2") (pinfunction "2_2") (pintype "passive"))
      (node (ref "R187") (pin "2") (pinfunction "2_2") (pintype "passive"))
      (node (ref "R188") (pin "1") (pinfunction "1_1") (pintype "passive"))
      (node (ref "R189") (pin "2") (pinfunction "2_2") (pintype "passive"))
    )
    (net (code "29") (name "Net-(C116-Pad1)") (class "Default")
      (node (ref "C116") (pin "1") (pinfunction "1_1") (pintype "passive"))
      (node (ref "R180") (pin "2") (pinfunction "2_2") (pintype "passive"))
      (node (ref "R190") (pin "1") (pinfunction "1_1") (pintype "passive"))
      (node (ref "R191") (pin "1") (pinfunction "1_1") (pintype "passive"))
    )
    (net (code "30") (name "Net-(R14-Pad2)") (class "Default")
      (node (ref "R14") (pin "2") (pinfunction "2_2") (pintype "passive"))
      (node (ref "R18") (pin "1") (pinfunction "1_1") (pintype "passive"))
    )
    (net (code "31") (name "Net-(R15-Pad2)") (class "Default")
      (node (ref "R15") (pin "2") (pinfunction "2_2") (pintype "passive"))
      (node (ref "R19") (pin "1") (pinfunction "1_1") (pintype "passive"))
    )
    (net (code "32") (name "Net-(R16-Pad2)") (class "Default")
      (node (ref "R16") (pin "2") (pinfunction "2_2") (pintype "passive"))
      (node (ref "R20") (pin "1") (pinfunction "1_1") (pintype "passive"))
    )
    (net (code "33") (name "Net-(R18-Pad2)") (class "Default")
      (node (ref "R18") (pin "2") (pinfunction "2_2") (pintype "passive"))
      (node (ref "R22") (pin "1") (pinfunction "1_1") (pintype "passive"))
    )
    (net (code "34") (name "Net-(R19-Pad2)") (class "Default")
      (node (ref "R19") (pin "2") (pinfunction "2_2") (pintype "passive"))
      (node (ref "R23") (pin "1") (pinfunction "1_1") (pintype "passive"))
    )
    (net (code "35") (name "Net-(R20-Pad2)") (class "Default")
      (node (ref "R20") (pin "2") (pinfunction "2_2") (pintype "passive"))
      (node (ref "R24") (pin "1") (pinfunction "1_1") (pintype "passive"))
    )
    (net (code "36") (name "Net-(R22-Pad2)") (class "Default")
      (node (ref "R22") (pin "2") (pinfunction "2_2") (pintype "passive"))
      (node (ref "R26") (pin "1") (pinfunction "1_1") (pintype "passive"))
    )
    (net (code "37") (name "Net-(R23-Pad2)") (class "Default")
      (node (ref "R23") (pin "2") (pinfunction "2_2") (pintype "passive"))
      (node (ref "R27") (pin "1") (pinfunction "1_1") (pintype "passive"))
    )
    (net (code "38") (name "Net-(R24-Pad2)") (class "Default")
      (node (ref "R24") (pin "2") (pinfunction "2_2") (pintype "passive"))
      (node (ref "R28") (pin "1") (pinfunction "1_1") (pintype "passive"))
    )
    (net (code "39") (name "Net-(R26-Pad2)") (class "Default")
      (node (ref "R26") (pin "2") (pinfunction "2_2") (pintype "passive"))
      (node (ref "R30") (pin "1") (pinfunction "1_1") (pintype "passive"))
    )
    (net (code "40") (name "Net-(R27-Pad2)") (class "Default")
      (node (ref "R27") (pin "2") (pinfunction "2_2") (pintype "passive"))
      (node (ref "R31") (pin "1") (pinfunction "1_1") (pintype "passive"))
    )
    (net (code "41") (name "Net-(R28-Pad2)") (class "Default")
      (node (ref "R28") (pin "2") (pinfunction "2_2") (pintype "passive"))
      (node (ref "R32") (pin "1") (pinfunction "1_1") (pintype "passive"))
    )
    (net (code "42") (name "Net-(R30-Pad2)") (class "Default")
      (node (ref "R30") (pin "2") (pinfunction "2_2") (pintype "passive"))
      (node (ref "R34") (pin "1") (pinfunction "1_1") (pintype "passive"))
    )
    (net (code "43") (name "Net-(R31-Pad2)") (class "Default")
      (node (ref "R31") (pin "2") (pinfunction "2_2") (pintype "passive"))
      (node (ref "R35") (pin "1") (pinfunction "1_1") (pintype "passive"))
    )
    (net (code "44") (name "Net-(R32-Pad2)") (class "Default")
      (node (ref "R32") (pin "2") (pinfunction "2_2") (pintype "passive"))
      (node (ref "R36") (pin "1") (pinfunction "1_1") (pintype "passive"))
    )
    (net (code "45") (name "Net-(R157-Pad2)") (class "Default")
      (node (ref "R157") (pin "2") (pinfunction "2_2") (pintype "passive"))
      (node (ref "R161") (pin "1") (pinfunction "1_1") (pintype "passive"))
    )
    (net (code "46") (name "Net-(R158-Pad2)") (class "Default")
      (node (ref "R158") (pin "2") (pinfunction "2_2") (pintype "passive"))
      (node (ref "R162") (pin "1") (pinfunction "1_1") (pintype "passive"))
    )
    (net (code "47") (name "Net-(R159-Pad2)") (class "Default")
      (node (ref "R159") (pin "2") (pinfunction "2_2") (pintype "passive"))
      (node (ref "R163") (pin "1") (pinfunction "1_1") (pintype "passive"))
    )
    (net (code "48") (name "Net-(R161-Pad2)") (class "Default")
      (node (ref "R161") (pin "2") (pinfunction "2_2") (pintype "passive"))
      (node (ref "R165") (pin "1") (pinfunction "1_1") (pintype "passive"))
    )
    (net (code "49") (name "Net-(R162-Pad2)") (class "Default")
      (node (ref "R162") (pin "2") (pinfunction "2_2") (pintype "passive"))
      (node (ref "R166") (pin "1") (pinfunction "1_1") (pintype "passive"))
    )
    (net (code "50") (name "Net-(R163-Pad2)") (class "Default")
      (node (ref "R163") (pin "2") (pinfunction "2_2") (pintype "passive"))
      (node (ref "R167") (pin "1") (pinfunction "1_1") (pintype "passive"))
    )
    (net (code "51") (name "Net-(R165-Pad2)") (class "Default")
      (node (ref "R165") (pin "2") (pinfunction "2_2") (pintype "passive"))
      (node (ref "R169") (pin "1") (pinfunction "1_1") (pintype "passive"))
    )
    (net (code "52") (name "Net-(R166-Pad2)") (class "Default")
      (node (ref "R166") (pin "2") (pinfunction "2_2") (pintype "passive"))
      (node (ref "R170") (pin "1") (pinfunction "1_1") (pintype "passive"))
    )
    (net (code "53") (name "Net-(R167-Pad2)") (class "Default")
      (node (ref "R167") (pin "2") (pinfunction "2_2") (pintype "passive"))
      (node (ref "R171") (pin "1") (pinfunction "1_1") (pintype "passive"))
    )
    (net (code "54") (name "Net-(R169-Pad2)") (class "Default")
      (node (ref "R169") (pin "2") (pinfunction "2_2") (pintype "passive"))
      (node (ref "R173") (pin "1") (pinfunction "1_1") (pintype "passive"))
    )
    (net (code "55") (name "Net-(R170-Pad2)") (class "Default")
      (node (ref "R170") (pin "2") (pinfunction "2_2") (pintype "passive"))
      (node (ref "R174") (pin "1") (pinfunction "1_1") (pintype "passive"))
    )
    (net (code "56") (name "Net-(R171-Pad2)") (class "Default")
      (node (ref "R171") (pin "2") (pinfunction "2_2") (pintype "passive"))
      (node (ref "R175") (pin "1") (pinfunction "1_1") (pintype "passive"))
    )
    (net (code "57") (name "Net-(R173-Pad2)") (class "Default")
      (node (ref "R173") (pin "2") (pinfunction "2_2") (pintype "passive"))
      (node (ref "R177") (pin "1") (pinfunction "1_1") (pintype "passive"))
    )
    (net (code "58") (name "Net-(R174-Pad2)") (class "Default")
      (node (ref "R174") (pin "2") (pinfunction "2_2") (pintype "passive"))
      (node (ref "R178") (pin "1") (pinfunction "1_1") (pintype "passive"))
    )
    (net (code "59") (name "Net-(R175-Pad2)") (class "Default")
      (node (ref "R175") (pin "2") (pinfunction "2_2") (pintype "passive"))
      (node (ref "R179") (pin "1") (pinfunction "1_1") (pintype "passive"))
    )
    (net (code "60") (name "Net-(U1-+IN)") (class "Default")
      (node (ref "R37") (pin "2") (pinfunction "2_2") (pintype "passive"))
      (node (ref "U1") (pin "3") (pinfunction "+IN_3") (pintype "input"))
    )
    (net (code "61") (name "Net-(U1--IN)") (class "Default")
      (node (ref "R191") (pin "2") (pinfunction "2_2") (pintype "passive"))
      (node (ref "U1") (pin "4") (pinfunction "-IN_4") (pintype "input"))
    )
    (net (code "62") (name "Net-(U1-OUT)") (class "Default")
      (node (ref "C116") (pin "2") (pinfunction "2_2") (pintype "passive"))
      (node (ref "R190") (pin "2") (pinfunction "2_2") (pintype "passive"))
      (node (ref "R57") (pin "1") (pinfunction "1_1") (pintype "passive"))
      (node (ref "U1") (pin "1") (pinfunction "OUT_1") (pintype "output"))
    )
    (net (code "63") (name "Net-(U2-+IN)") (class "Default")
      (node (ref "R39") (pin "2") (pinfunction "2_2") (pintype "passive"))
      (node (ref "U2") (pin "3") (pinfunction "+IN_3") (pintype "input"))
    )
    (net (code "64") (name "Net-(U2--IN)") (class "Default")
      (node (ref "R188") (pin "2") (pinfunction "2_2") (pintype "passive"))
      (node (ref "U2") (pin "4") (pinfunction "-IN_4") (pintype "input"))
    )
    (net (code "65") (name "Net-(U2-OUT)") (class "Default")
      (node (ref "C115") (pin "2") (pinfunction "2_2") (pintype "passive"))
      (node (ref "R187") (pin "1") (pinfunction "1_1") (pintype "passive"))
      (node (ref "R54") (pin "1") (pinfunction "1_1") (pintype "passive"))
      (node (ref "U2") (pin "1") (pinfunction "OUT_1") (pintype "output"))
    )
    (net (code "66") (name "Net-(U3-+IN)") (class "Default")
      (node (ref "R41") (pin "2") (pinfunction "2_2") (pintype "passive"))
      (node (ref "U3") (pin "3") (pinfunction "+IN_3") (pintype "input"))
    )
    (net (code "67") (name "Net-(U3--IN)") (class "Default")
      (node (ref "R185") (pin "2") (pinfunction "2_2") (pintype "passive"))
      (node (ref "U3") (pin "4") (pinfunction "-IN_4") (pintype "input"))
    )
    (net (code "68") (name "Net-(U3-OUT)") (class "Default")
      (node (ref "C114") (pin "2") (pinfunction "2_2") (pintype "passive"))
      (node (ref "R184") (pin "1") (pinfunction "1_1") (pintype "passive"))
      (node (ref "R52") (pin "1") (pinfunction "1_1") (pintype "passive"))
      (node (ref "U3") (pin "1") (pinfunction "OUT_1") (pintype "output"))
    )
    (net (code "69") (name "Net-(U4-+IN)") (class "Default")
      (node (ref "R43") (pin "2") (pinfunction "2_2") (pintype "passive"))
      (node (ref "U4") (pin "3") (pinfunction "+IN_3") (pintype "input"))
    )
    (net (code "70") (name "Net-(U4--IN)") (class "Default")
      (node (ref "R182") (pin "2") (pinfunction "2_2") (pintype "passive"))
      (node (ref "U4") (pin "4") (pinfunction "-IN_4") (pintype "input"))
    )
    (net (code "71") (name "Net-(U4-OUT)") (class "Default")
      (node (ref "C113") (pin "2") (pinfunction "2_2") (pintype "passive"))
      (node (ref "R181") (pin "1") (pinfunction "1_1") (pintype "passive"))
      (node (ref "R51") (pin "1") (pinfunction "1_1") (pintype "passive"))
      (node (ref "U4") (pin "1") (pinfunction "OUT_1") (pintype "output"))
    )
    (net (code "72") (name "VDC_MEAS") (class "Default")
      (node (ref "C134") (pin "1") (pinfunction "1_1") (pintype "passive"))
      (node (ref "R57") (pin "2") (pinfunction "2_2") (pintype "passive"))
    )
    (net (code "73") (name "VU_MEAS") (class "Default")
      (node (ref "C125") (pin "1") (pinfunction "1_1") (pintype "passive"))
      (node (ref "R51") (pin "2") (pinfunction "2_2") (pintype "passive"))
    )
    (net (code "74") (name "VV_MEAS") (class "Default")
      (node (ref "C127") (pin "1") (pinfunction "1_1") (pintype "passive"))
      (node (ref "R52") (pin "2") (pinfunction "2_2") (pintype "passive"))
    )
    (net (code "75") (name "VW_MEAS") (class "Default")
      (node (ref "C129") (pin "1") (pinfunction "1_1") (pintype "passive"))
      (node (ref "R54") (pin "2") (pinfunction "2_2") (pintype "passive"))
    )
  )
)
